# Converter.net
KiCad netlist of a schematic drawn in Altium Designer
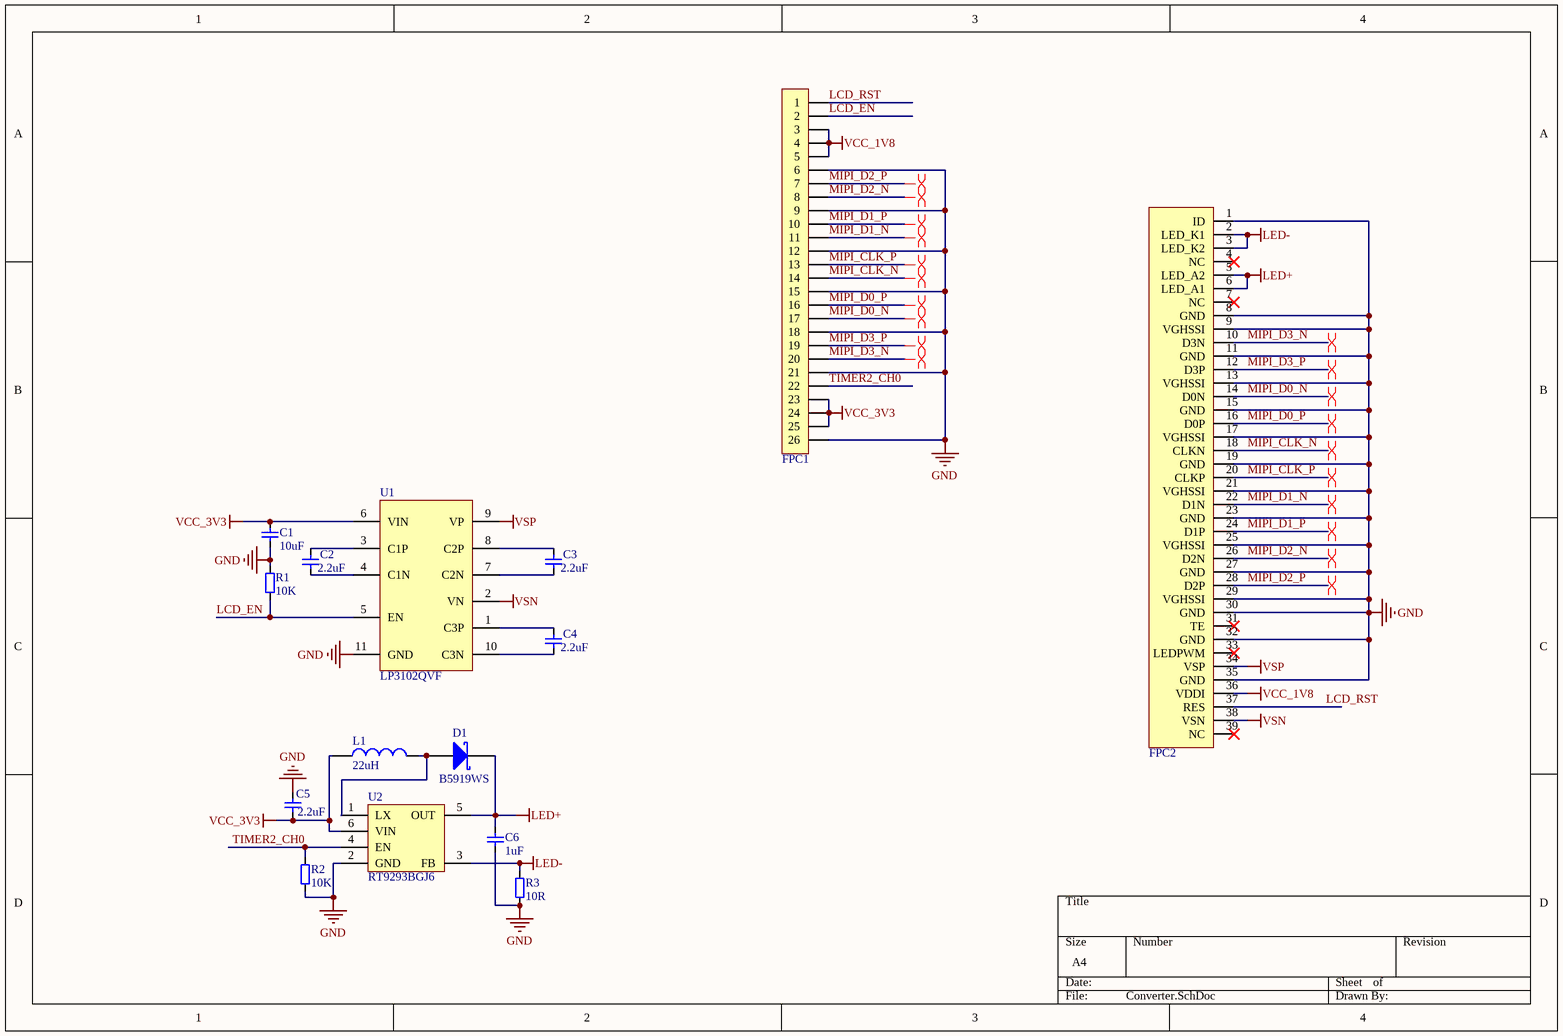
[diagram p0: Converter.SchDoc]

(export (version "E")
  (design (tool "Eeschema 10.0.6"))
  (components
    (comp (ref "C1")
      (value "10uF")
      (footprint "C0402_L")
      (description "贴片电容")
      (libsource (lib "0.1 - 电阻-电容-电感-磁珠-电位器") (part "C"))
    )
    (comp (ref "C2")
      (value "2.2uF")
      (footprint "C0402_L")
      (description "贴片电容")
      (libsource (lib "0.1 - 电阻-电容-电感-磁珠-电位器") (part "C"))
    )
    (comp (ref "C3")
      (value "2.2uF")
      (footprint "C0402_L")
      (description "贴片电容")
      (libsource (lib "0.1 - 电阻-电容-电感-磁珠-电位器") (part "C"))
    )
    (comp (ref "C4")
      (value "2.2uF")
      (footprint "C0402_L")
      (description "贴片电容")
      (libsource (lib "0.1 - 电阻-电容-电感-磁珠-电位器") (part "C"))
    )
    (comp (ref "C5")
      (value "2.2uF")
      (footprint "C0402_L")
      (description "贴片电容")
      (libsource (lib "0.1 - 电阻-电容-电感-磁珠-电位器") (part "C"))
    )
    (comp (ref "C6")
      (value "1uF")
      (footprint "C0402_L")
      (description "贴片电容")
      (libsource (lib "0.1 - 电阻-电容-电感-磁珠-电位器") (part "C"))
    )
    (comp (ref "D1")
      (value "B5919WS")
      (footprint "SOD-323")
      (description "肖特基二极管")
      (libsource (lib "0.2 - 二极管-TVS-ESD-整流桥") (part "1N5819"))
    )
    (comp (ref "FPC1")
      (value "FPC1.0-26P")
      (footprint "FPC0.5 2H-WS-26P")
      (description "FPC连接器")
      (fields (field (name "版权归属") "源创客"))
      (libsource (lib "4.14 - FPC连接器") (part "FPC-26P"))
    )
    (comp (ref "FPC2")
      (value "LQ055T3SX02Z")
      (footprint "FPC0.5 2H-WS-39P")
      (description "5.5寸显示屏")
      (fields (field (name "版权归属") "源创客"))
      (libsource (lib "User") (part "LQ055T3SX02Z"))
    )
    (comp (ref "L1")
      (value "22uH")
      (footprint "SWPA5040")
      (description "贴片小功率电感")
      (libsource (lib "0.1 - 电阻-电容-电感-磁珠-电位器") (part "L"))
    )
    (comp (ref "R1")
      (value "10K")
      (footprint "R0402_L")
      (description "贴片电阻")
      (libsource (lib "0.1 - 电阻-电容-电感-磁珠-电位器") (part "R"))
    )
    (comp (ref "R2")
      (value "10K")
      (footprint "R0402_L")
      (description "贴片电阻")
      (libsource (lib "0.1 - 电阻-电容-电感-磁珠-电位器") (part "R"))
    )
    (comp (ref "R3")
      (value "10R")
      (footprint "R0603_L")
      (description "贴片电阻")
      (libsource (lib "0.1 - 电阻-电容-电感-磁珠-电位器") (part "R"))
    )
    (comp (ref "U1")
      (value "LP3102QVF")
      (footprint "LP3102")
      (description "C517005")
      (libsource (lib "User") (part "LP3102QVF"))
    )
    (comp (ref "U2")
      (value "RT9293BGJ6")
      (footprint "RT9293BGJ6")
      (description "异步升压的LED驱动器 C36462")
      (libsource (lib "User") (part "RT9293BGJ6"))
    )
  )
  (nets
    (net (code "1") (name "/LCD_EN") (class "Default")
      (node (ref "FPC1") (pin "2") (pinfunction "2_2") (pintype "passive"))
      (node (ref "R1") (pin "2") (pinfunction "2_2") (pintype "passive"))
      (node (ref "U1") (pin "5") (pinfunction "EN_5") (pintype "passive"))
    )
    (net (code "2") (name "/LCD_RST") (class "Default")
      (node (ref "FPC1") (pin "1") (pinfunction "1_1") (pintype "passive"))
      (node (ref "FPC2") (pin "37") (pinfunction "RES_37") (pintype "passive"))
    )
    (net (code "3") (name "/MIPI_CLK_N") (class "Default")
      (node (ref "FPC1") (pin "14") (pinfunction "14_14") (pintype "passive"))
      (node (ref "FPC2") (pin "18") (pinfunction "CLKN_18") (pintype "passive"))
    )
    (net (code "4") (name "/MIPI_CLK_P") (class "Default")
      (node (ref "FPC1") (pin "13") (pinfunction "13_13") (pintype "passive"))
      (node (ref "FPC2") (pin "20") (pinfunction "CLKP_20") (pintype "passive"))
    )
    (net (code "5") (name "/MIPI_D0_N") (class "Default")
      (node (ref "FPC1") (pin "17") (pinfunction "17_17") (pintype "passive"))
      (node (ref "FPC2") (pin "14") (pinfunction "D0N_14") (pintype "passive"))
    )
    (net (code "6") (name "/MIPI_D0_P") (class "Default")
      (node (ref "FPC1") (pin "16") (pinfunction "16_16") (pintype "passive"))
      (node (ref "FPC2") (pin "16") (pinfunction "D0P_16") (pintype "passive"))
    )
    (net (code "7") (name "/MIPI_D1_N") (class "Default")
      (node (ref "FPC1") (pin "11") (pinfunction "11_11") (pintype "passive"))
      (node (ref "FPC2") (pin "22") (pinfunction "D1N_22") (pintype "passive"))
    )
    (net (code "8") (name "/MIPI_D1_P") (class "Default")
      (node (ref "FPC1") (pin "10") (pinfunction "10_10") (pintype "passive"))
      (node (ref "FPC2") (pin "24") (pinfunction "D1P_24") (pintype "passive"))
    )
    (net (code "9") (name "/MIPI_D2_N") (class "Default")
      (node (ref "FPC1") (pin "8") (pinfunction "8_8") (pintype "passive"))
      (node (ref "FPC2") (pin "26") (pinfunction "D2N_26") (pintype "passive"))
    )
    (net (code "10") (name "/MIPI_D2_P") (class "Default")
      (node (ref "FPC1") (pin "7") (pinfunction "7_7") (pintype "passive"))
      (node (ref "FPC2") (pin "28") (pinfunction "D2P_28") (pintype "passive"))
    )
    (net (code "11") (name "/MIPI_D3_N") (class "Default")
      (node (ref "FPC1") (pin "20") (pinfunction "20_20") (pintype "passive"))
      (node (ref "FPC2") (pin "10") (pinfunction "D3N_10") (pintype "passive"))
    )
    (net (code "12") (name "/MIPI_D3_P") (class "Default")
      (node (ref "FPC1") (pin "19") (pinfunction "19_19") (pintype "passive"))
      (node (ref "FPC2") (pin "12") (pinfunction "D3P_12") (pintype "passive"))
    )
    (net (code "13") (name "/TIMER2_CH0") (class "Default")
      (node (ref "FPC1") (pin "22") (pinfunction "22_22") (pintype "passive"))
      (node (ref "R2") (pin "1") (pinfunction "1_1") (pintype "passive"))
      (node (ref "U2") (pin "4") (pinfunction "EN_4") (pintype "passive"))
    )
    (net (code "14") (name "GND") (class "Default")
      (node (ref "C1") (pin "2") (pinfunction "2_2") (pintype "passive"))
      (node (ref "C5") (pin "1") (pinfunction "1_1") (pintype "passive"))
      (node (ref "C6") (pin "1") (pinfunction "1_1") (pintype "passive"))
      (node (ref "FPC1") (pin "12") (pinfunction "12_12") (pintype "passive"))
      (node (ref "FPC1") (pin "15") (pinfunction "15_15") (pintype "passive"))
      (node (ref "FPC1") (pin "18") (pinfunction "18_18") (pintype "passive"))
      (node (ref "FPC1") (pin "21") (pinfunction "21_21") (pintype "passive"))
      (node (ref "FPC1") (pin "26") (pinfunction "26_26") (pintype "passive"))
      (node (ref "FPC1") (pin "6") (pinfunction "6_6") (pintype "passive"))
      (node (ref "FPC1") (pin "9") (pinfunction "9_9") (pintype "passive"))
      (node (ref "FPC2") (pin "1") (pinfunction "ID_1") (pintype "passive"))
      (node (ref "FPC2") (pin "11") (pinfunction "GND_11") (pintype "passive"))
      (node (ref "FPC2") (pin "13") (pinfunction "VGHSSI_13") (pintype "passive"))
      (node (ref "FPC2") (pin "15") (pinfunction "GND_15") (pintype "passive"))
      (node (ref "FPC2") (pin "17") (pinfunction "VGHSSI_17") (pintype "passive"))
      (node (ref "FPC2") (pin "19") (pinfunction "GND_19") (pintype "passive"))
      (node (ref "FPC2") (pin "21") (pinfunction "VGHSSI_21") (pintype "passive"))
      (node (ref "FPC2") (pin "23") (pinfunction "GND_23") (pintype "passive"))
      (node (ref "FPC2") (pin "25") (pinfunction "VGHSSI_25") (pintype "passive"))
      (node (ref "FPC2") (pin "27") (pinfunction "GND_27") (pintype "passive"))
      (node (ref "FPC2") (pin "29") (pinfunction "VGHSSI_29") (pintype "passive"))
      (node (ref "FPC2") (pin "30") (pinfunction "GND_30") (pintype "passive"))
      (node (ref "FPC2") (pin "32") (pinfunction "GND_32") (pintype "passive"))
      (node (ref "FPC2") (pin "35") (pinfunction "GND_35") (pintype "passive"))
      (node (ref "FPC2") (pin "8") (pinfunction "GND_8") (pintype "passive"))
      (node (ref "FPC2") (pin "9") (pinfunction "VGHSSI_9") (pintype "passive"))
      (node (ref "R1") (pin "1") (pinfunction "1_1") (pintype "passive"))
      (node (ref "R2") (pin "2") (pinfunction "2_2") (pintype "passive"))
      (node (ref "R3") (pin "2") (pinfunction "2_2") (pintype "passive"))
      (node (ref "U1") (pin "11") (pinfunction "GND_11") (pintype "passive"))
      (node (ref "U2") (pin "2") (pinfunction "GND_2") (pintype "passive"))
    )
    (net (code "15") (name "LED+") (class "Default")
      (node (ref "C6") (pin "2") (pinfunction "2_2") (pintype "passive"))
      (node (ref "D1") (pin "2") (pinfunction "K_2") (pintype "passive"))
      (node (ref "FPC2") (pin "5") (pinfunction "LED_A2_5") (pintype "passive"))
      (node (ref "FPC2") (pin "6") (pinfunction "LED_A1_6") (pintype "passive"))
      (node (ref "U2") (pin "5") (pinfunction "OUT_5") (pintype "passive"))
    )
    (net (code "16") (name "LED-") (class "Default")
      (node (ref "FPC2") (pin "2") (pinfunction "LED_K1_2") (pintype "passive"))
      (node (ref "FPC2") (pin "3") (pinfunction "LED_K2_3") (pintype "passive"))
      (node (ref "R3") (pin "1") (pinfunction "1_1") (pintype "passive"))
      (node (ref "U2") (pin "3") (pinfunction "FB_3") (pintype "passive"))
    )
    (net (code "17") (name "Net-(D1-A)") (class "Default")
      (node (ref "D1") (pin "1") (pinfunction "A_1") (pintype "passive"))
      (node (ref "L1") (pin "2") (pinfunction "2_2") (pintype "passive"))
      (node (ref "U2") (pin "1") (pinfunction "LX_1") (pintype "passive"))
    )
    (net (code "18") (name "Net-(U1-C1N)") (class "Default")
      (node (ref "C2") (pin "1") (pinfunction "1_1") (pintype "passive"))
      (node (ref "U1") (pin "4") (pinfunction "C1N_4") (pintype "passive"))
    )
    (net (code "19") (name "Net-(U1-C1P)") (class "Default")
      (node (ref "C2") (pin "2") (pinfunction "2_2") (pintype "passive"))
      (node (ref "U1") (pin "3") (pinfunction "C1P_3") (pintype "passive"))
    )
    (net (code "20") (name "Net-(U1-C2N)") (class "Default")
      (node (ref "C3") (pin "1") (pinfunction "1_1") (pintype "passive"))
      (node (ref "U1") (pin "7") (pinfunction "C2N_7") (pintype "passive"))
    )
    (net (code "21") (name "Net-(U1-C2P)") (class "Default")
      (node (ref "C3") (pin "2") (pinfunction "2_2") (pintype "passive"))
      (node (ref "U1") (pin "8") (pinfunction "C2P_8") (pintype "passive"))
    )
    (net (code "22") (name "Net-(U1-C3N)") (class "Default")
      (node (ref "C4") (pin "1") (pinfunction "1_1") (pintype "passive"))
      (node (ref "U1") (pin "10") (pinfunction "C3N_10") (pintype "passive"))
    )
    (net (code "23") (name "Net-(U1-C3P)") (class "Default")
      (node (ref "C4") (pin "2") (pinfunction "2_2") (pintype "passive"))
      (node (ref "U1") (pin "1") (pinfunction "C3P_1") (pintype "passive"))
    )
    (net (code "24") (name "VCC_1V8") (class "Default")
      (node (ref "FPC1") (pin "3") (pinfunction "3_3") (pintype "passive"))
      (node (ref "FPC1") (pin "4") (pinfunction "4_4") (pintype "passive"))
      (node (ref "FPC1") (pin "5") (pinfunction "5_5") (pintype "passive"))
      (node (ref "FPC2") (pin "36") (pinfunction "VDDI_36") (pintype "passive"))
    )
    (net (code "25") (name "VCC_3V3") (class "Default")
      (node (ref "C1") (pin "1") (pinfunction "1_1") (pintype "passive"))
      (node (ref "C5") (pin "2") (pinfunction "2_2") (pintype "passive"))
      (node (ref "FPC1") (pin "23") (pinfunction "23_23") (pintype "passive"))
      (node (ref "FPC1") (pin "24") (pinfunction "24_24") (pintype "passive"))
      (node (ref "FPC1") (pin "25") (pinfunction "25_25") (pintype "passive"))
      (node (ref "L1") (pin "1") (pinfunction "1_1") (pintype "passive"))
      (node (ref "U1") (pin "6") (pinfunction "VIN_6") (pintype "passive"))
      (node (ref "U2") (pin "6") (pinfunction "VIN_6") (pintype "passive"))
    )
    (net (code "26") (name "VSN") (class "Default")
      (node (ref "FPC2") (pin "38") (pinfunction "VSN_38") (pintype "passive"))
      (node (ref "U1") (pin "2") (pinfunction "VN_2") (pintype "passive"))
    )
    (net (code "27") (name "VSP") (class "Default")
      (node (ref "FPC2") (pin "34") (pinfunction "VSP_34") (pintype "passive"))
      (node (ref "U1") (pin "9") (pinfunction "VP_9") (pintype "passive"))
    )
    (net (code "28") (name "unconnected-(FPC2-LEDPWM-Pad33)") (class "Default")
      (node (ref "FPC2") (pin "33") (pinfunction "LEDPWM_33") (pintype "passive+no_connect"))
    )
    (net (code "29") (name "unconnected-(FPC2-NC-Pad4)") (class "Default")
      (node (ref "FPC2") (pin "4") (pinfunction "NC_4") (pintype "passive+no_connect"))
    )
    (net (code "30") (name "unconnected-(FPC2-NC-Pad7)") (class "Default")
      (node (ref "FPC2") (pin "7") (pinfunction "NC_7") (pintype "passive+no_connect"))
    )
    (net (code "31") (name "unconnected-(FPC2-NC-Pad39)") (class "Default")
      (node (ref "FPC2") (pin "39") (pinfunction "NC_39") (pintype "passive+no_connect"))
    )
    (net (code "32") (name "unconnected-(FPC2-TE-Pad31)") (class "Default")
      (node (ref "FPC2") (pin "31") (pinfunction "TE_31") (pintype "passive+no_connect"))
    )
  )
)
